# SCH_Instrumenta_o-Eletronica.net
KiCad netlist of a schematic drawn in EasyEDA
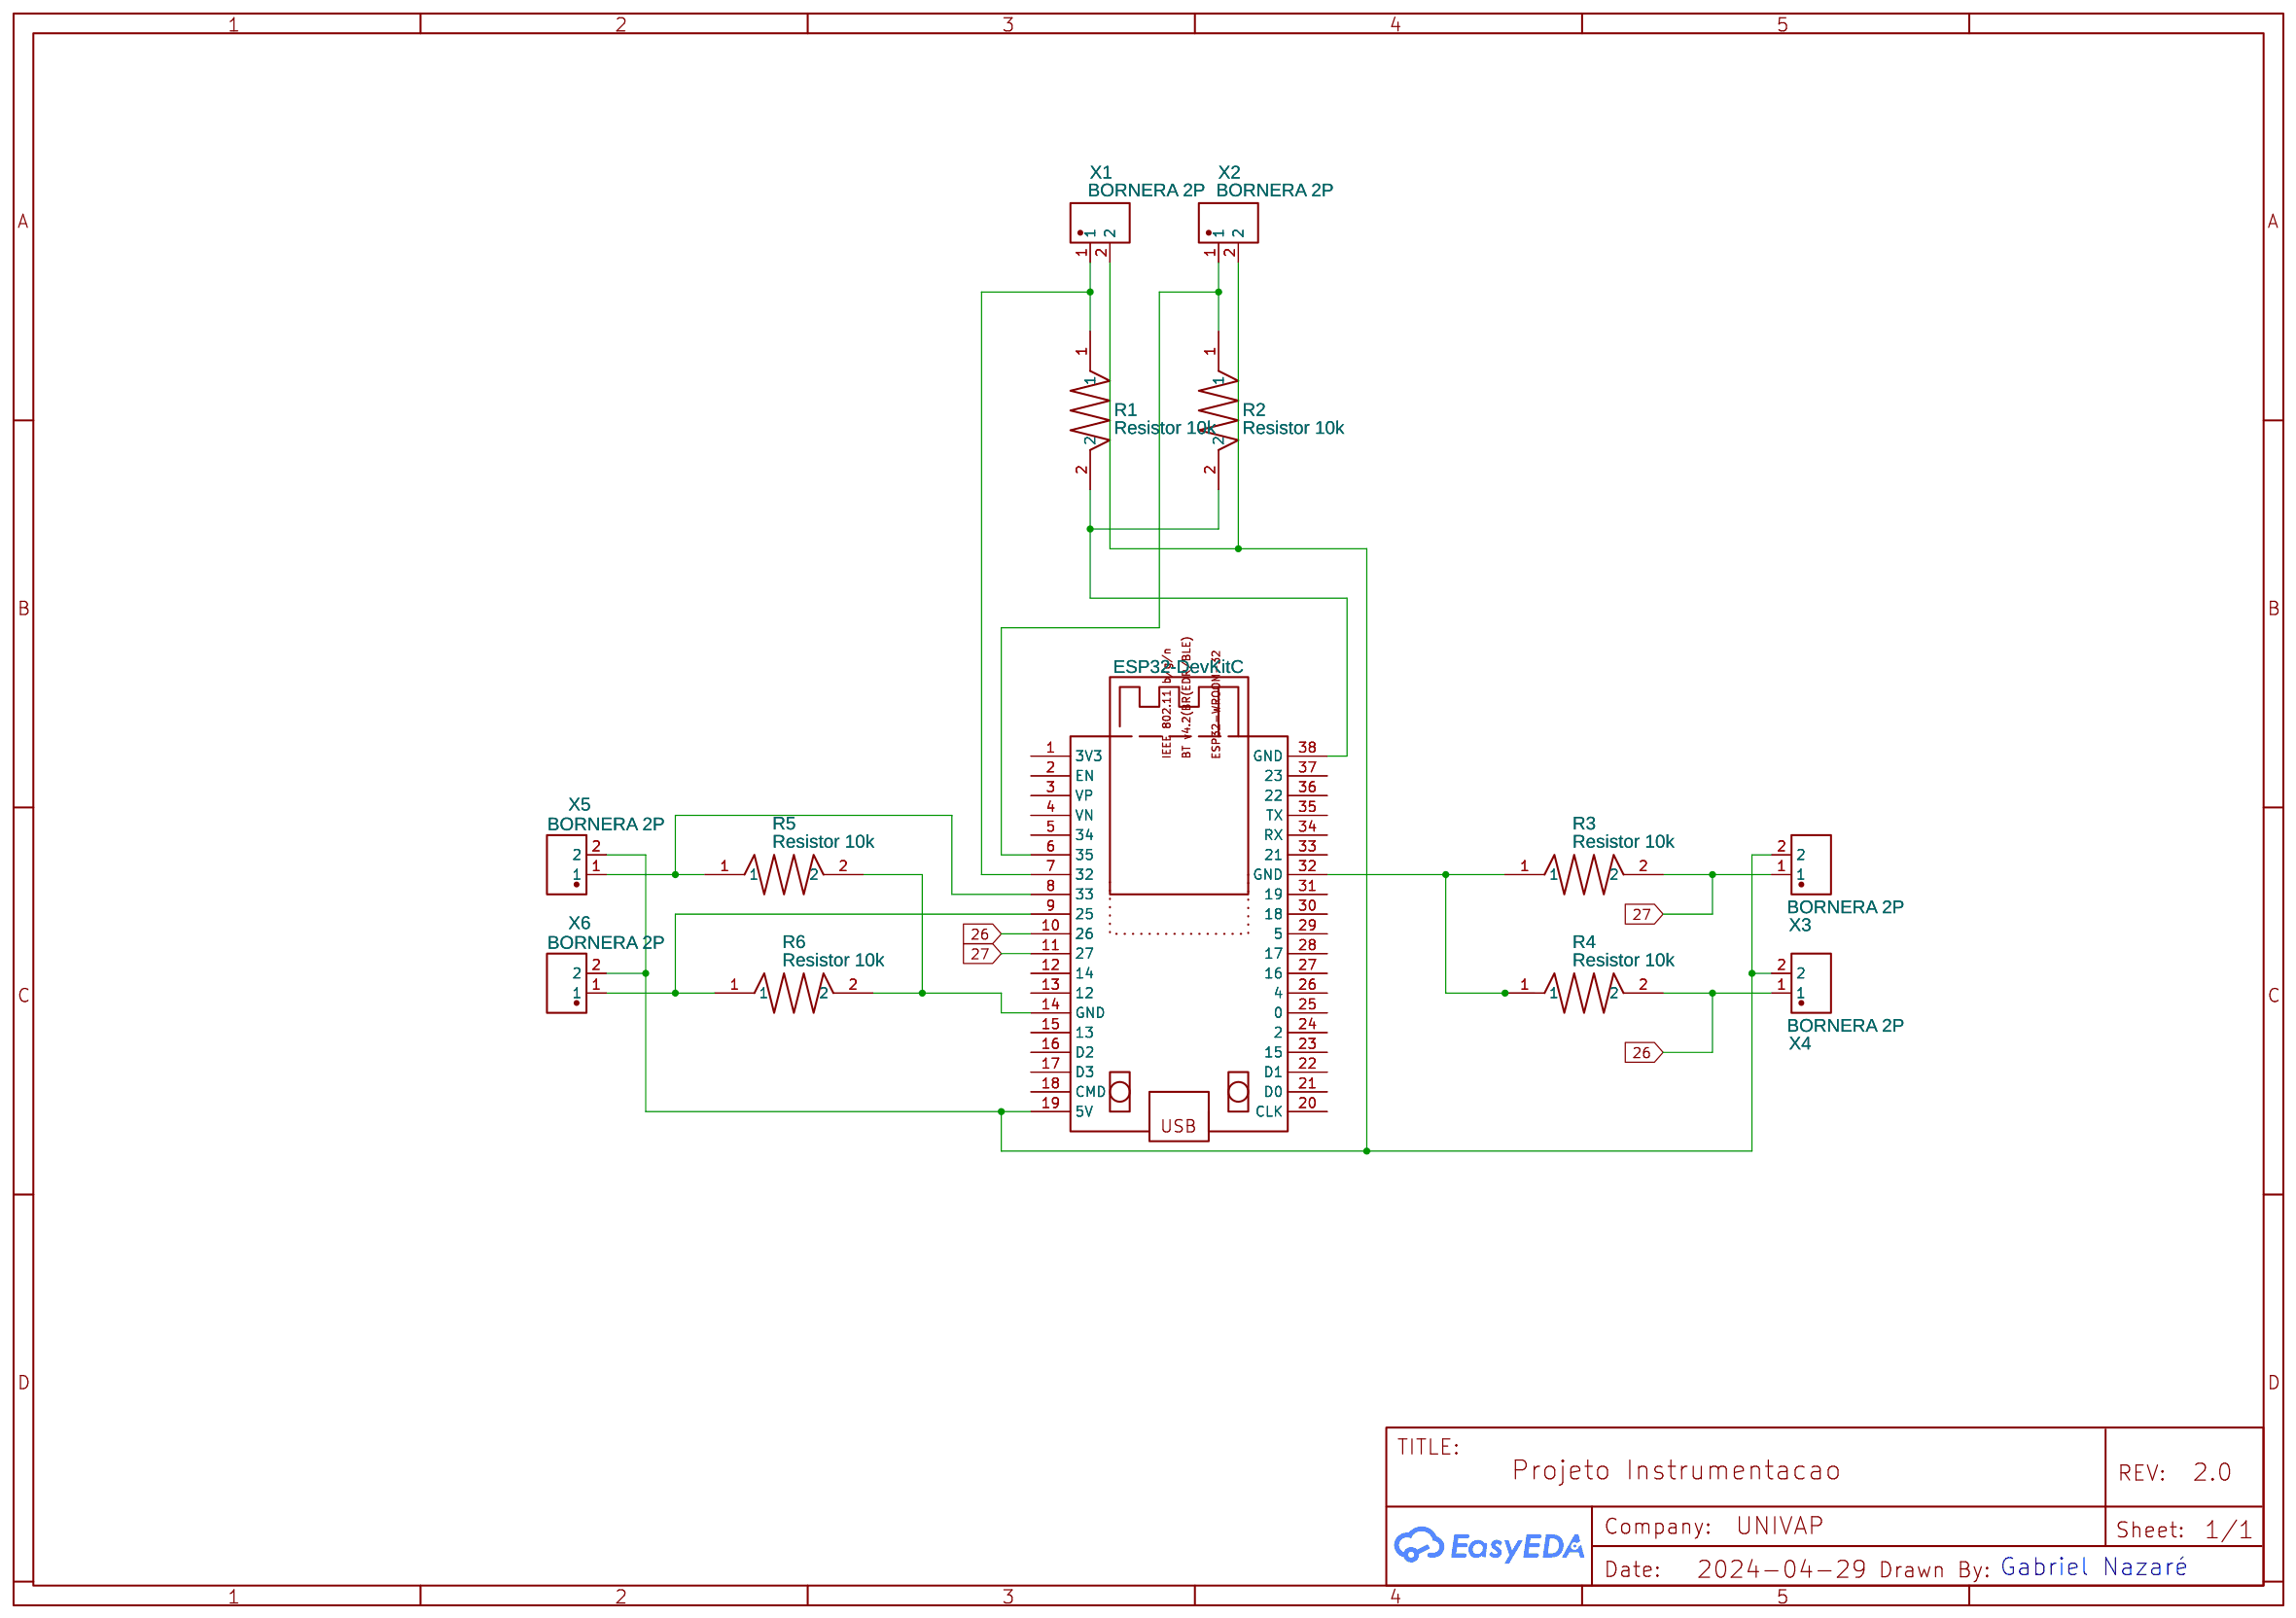
[diagram p0: schematic sheet]

(export (version "E")
  (design (tool "Eeschema 10.0.6"))
  (components
    (comp (ref "R1") (value "Resistor 10k") (libsource (lib "") (part "Resistor 10k_1")))
    (comp (ref "R2") (value "Resistor 10k") (libsource (lib "") (part "Resistor 10k_1")))
    (comp (ref "R3") (value "Resistor 10k") (libsource (lib "") (part "Resistor 10k")))
    (comp (ref "R4") (value "Resistor 10k") (libsource (lib "") (part "Resistor 10k")))
    (comp (ref "R5") (value "Resistor 10k") (libsource (lib "") (part "Resistor 10k")))
    (comp (ref "R6") (value "Resistor 10k") (libsource (lib "") (part "Resistor 10k")))
    (comp (ref "U1")
      (value "ESP32-DevKitC")
      (fields (field (name "Manufacturer") "Espressif Systems"))
      (libsource (lib "") (part "ESP32-DevKitC"))
    )
    (comp (ref "X1") (value "BORNERA 2P") (libsource (lib "") (part "BORNERA 2P_2")))
    (comp (ref "X2") (value "BORNERA 2P") (libsource (lib "") (part "BORNERA 2P_2")))
    (comp (ref "X3") (value "BORNERA 2P") (libsource (lib "") (part "BORNERA 2P")))
    (comp (ref "X4") (value "BORNERA 2P") (libsource (lib "") (part "BORNERA 2P")))
    (comp (ref "X5") (value "BORNERA 2P") (libsource (lib "") (part "BORNERA 2P_1")))
    (comp (ref "X6") (value "BORNERA 2P") (libsource (lib "") (part "BORNERA 2P_1")))
  )
  (nets
    (net (code "1") (name "26") (class "Default")
      (node (ref "R4") (pin "2") (pinfunction "2_2") (pintype "unspecified"))
      (node (ref "U1") (pin "10") (pinfunction "26_10") (pintype "unspecified"))
      (node (ref "X4") (pin "1") (pinfunction "1_1") (pintype "unspecified"))
    )
    (net (code "2") (name "27") (class "Default")
      (node (ref "R3") (pin "2") (pinfunction "2_2") (pintype "unspecified"))
      (node (ref "U1") (pin "11") (pinfunction "27_11") (pintype "unspecified"))
      (node (ref "X3") (pin "1") (pinfunction "1_1") (pintype "unspecified"))
    )
    (net (code "3") (name "Net-(R1-Pad2)") (class "Default")
      (node (ref "R1") (pin "2") (pinfunction "2_2") (pintype "unspecified"))
      (node (ref "R2") (pin "2") (pinfunction "2_2") (pintype "unspecified"))
      (node (ref "U1") (pin "38") (pinfunction "GND_38") (pintype "unspecified"))
    )
    (net (code "4") (name "Net-(R3-Pad1)") (class "Default")
      (node (ref "R3") (pin "1") (pinfunction "1_1") (pintype "unspecified"))
      (node (ref "R4") (pin "1") (pinfunction "1_1") (pintype "unspecified"))
      (node (ref "U1") (pin "32") (pinfunction "GND_32") (pintype "unspecified"))
    )
    (net (code "5") (name "Net-(R5-Pad2)") (class "Default")
      (node (ref "R5") (pin "2") (pinfunction "2_2") (pintype "unspecified"))
      (node (ref "R6") (pin "2") (pinfunction "2_2") (pintype "unspecified"))
      (node (ref "U1") (pin "14") (pinfunction "GND_14") (pintype "unspecified"))
    )
    (net (code "6") (name "Net-(U1-5V)") (class "Default")
      (node (ref "U1") (pin "19") (pinfunction "5V_19") (pintype "unspecified"))
      (node (ref "X1") (pin "2") (pinfunction "2_2") (pintype "unspecified"))
      (node (ref "X2") (pin "2") (pinfunction "2_2") (pintype "unspecified"))
      (node (ref "X3") (pin "2") (pinfunction "2_2") (pintype "unspecified"))
      (node (ref "X4") (pin "2") (pinfunction "2_2") (pintype "unspecified"))
      (node (ref "X5") (pin "2") (pinfunction "2_2") (pintype "unspecified"))
      (node (ref "X6") (pin "2") (pinfunction "2_2") (pintype "unspecified"))
    )
    (net (code "7") (name "Net-(U1-25)") (class "Default")
      (node (ref "R6") (pin "1") (pinfunction "1_1") (pintype "unspecified"))
      (node (ref "U1") (pin "9") (pinfunction "25_9") (pintype "unspecified"))
      (node (ref "X6") (pin "1") (pinfunction "1_1") (pintype "unspecified"))
    )
    (net (code "8") (name "Net-(U1-32)") (class "Default")
      (node (ref "R1") (pin "1") (pinfunction "1_1") (pintype "unspecified"))
      (node (ref "U1") (pin "7") (pinfunction "32_7") (pintype "unspecified"))
      (node (ref "X1") (pin "1") (pinfunction "1_1") (pintype "unspecified"))
    )
    (net (code "9") (name "Net-(U1-33)") (class "Default")
      (node (ref "R5") (pin "1") (pinfunction "1_1") (pintype "unspecified"))
      (node (ref "U1") (pin "8") (pinfunction "33_8") (pintype "unspecified"))
      (node (ref "X5") (pin "1") (pinfunction "1_1") (pintype "unspecified"))
    )
    (net (code "10") (name "Net-(U1-35)") (class "Default")
      (node (ref "R2") (pin "1") (pinfunction "1_1") (pintype "unspecified"))
      (node (ref "U1") (pin "6") (pinfunction "35_6") (pintype "unspecified"))
      (node (ref "X2") (pin "1") (pinfunction "1_1") (pintype "unspecified"))
    )
    (net (code "11") (name "unconnected-(U1-0-Pad25)") (class "Default")
      (node (ref "U1") (pin "25") (pinfunction "0_25") (pintype "unspecified"))
    )
    (net (code "12") (name "unconnected-(U1-2-Pad24)") (class "Default")
      (node (ref "U1") (pin "24") (pinfunction "2_24") (pintype "unspecified"))
    )
    (net (code "13") (name "unconnected-(U1-3V3-Pad1)") (class "Default")
      (node (ref "U1") (pin "1") (pinfunction "3V3_1") (pintype "unspecified"))
    )
    (net (code "14") (name "unconnected-(U1-4-Pad26)") (class "Default")
      (node (ref "U1") (pin "26") (pinfunction "4_26") (pintype "unspecified"))
    )
    (net (code "15") (name "unconnected-(U1-5-Pad29)") (class "Default")
      (node (ref "U1") (pin "29") (pinfunction "5_29") (pintype "unspecified"))
    )
    (net (code "16") (name "unconnected-(U1-12-Pad13)") (class "Default")
      (node (ref "U1") (pin "13") (pinfunction "12_13") (pintype "unspecified"))
    )
    (net (code "17") (name "unconnected-(U1-13-Pad15)") (class "Default")
      (node (ref "U1") (pin "15") (pinfunction "13_15") (pintype "unspecified"))
    )
    (net (code "18") (name "unconnected-(U1-14-Pad12)") (class "Default")
      (node (ref "U1") (pin "12") (pinfunction "14_12") (pintype "unspecified"))
    )
    (net (code "19") (name "unconnected-(U1-15-Pad23)") (class "Default")
      (node (ref "U1") (pin "23") (pinfunction "15_23") (pintype "unspecified"))
    )
    (net (code "20") (name "unconnected-(U1-16-Pad27)") (class "Default")
      (node (ref "U1") (pin "27") (pinfunction "16_27") (pintype "unspecified"))
    )
    (net (code "21") (name "unconnected-(U1-17-Pad28)") (class "Default")
      (node (ref "U1") (pin "28") (pinfunction "17_28") (pintype "unspecified"))
    )
    (net (code "22") (name "unconnected-(U1-18-Pad30)") (class "Default")
      (node (ref "U1") (pin "30") (pinfunction "18_30") (pintype "unspecified"))
    )
    (net (code "23") (name "unconnected-(U1-19-Pad31)") (class "Default")
      (node (ref "U1") (pin "31") (pinfunction "19_31") (pintype "unspecified"))
    )
    (net (code "24") (name "unconnected-(U1-21-Pad33)") (class "Default")
      (node (ref "U1") (pin "33") (pinfunction "21_33") (pintype "unspecified"))
    )
    (net (code "25") (name "unconnected-(U1-22-Pad36)") (class "Default")
      (node (ref "U1") (pin "36") (pinfunction "22_36") (pintype "unspecified"))
    )
    (net (code "26") (name "unconnected-(U1-23-Pad37)") (class "Default")
      (node (ref "U1") (pin "37") (pinfunction "23_37") (pintype "unspecified"))
    )
    (net (code "27") (name "unconnected-(U1-34-Pad5)") (class "Default")
      (node (ref "U1") (pin "5") (pinfunction "34_5") (pintype "unspecified"))
    )
    (net (code "28") (name "unconnected-(U1-CLK-Pad20)") (class "Default")
      (node (ref "U1") (pin "20") (pinfunction "CLK_20") (pintype "unspecified"))
    )
    (net (code "29") (name "unconnected-(U1-CMD-Pad18)") (class "Default")
      (node (ref "U1") (pin "18") (pinfunction "CMD_18") (pintype "unspecified"))
    )
    (net (code "30") (name "unconnected-(U1-D0-Pad21)") (class "Default")
      (node (ref "U1") (pin "21") (pinfunction "D0_21") (pintype "unspecified"))
    )
    (net (code "31") (name "unconnected-(U1-D1-Pad22)") (class "Default")
      (node (ref "U1") (pin "22") (pinfunction "D1_22") (pintype "unspecified"))
    )
    (net (code "32") (name "unconnected-(U1-D2-Pad16)") (class "Default")
      (node (ref "U1") (pin "16") (pinfunction "D2_16") (pintype "unspecified"))
    )
    (net (code "33") (name "unconnected-(U1-D3-Pad17)") (class "Default")
      (node (ref "U1") (pin "17") (pinfunction "D3_17") (pintype "unspecified"))
    )
    (net (code "34") (name "unconnected-(U1-EN-Pad2)") (class "Default")
      (node (ref "U1") (pin "2") (pinfunction "EN_2") (pintype "unspecified"))
    )
    (net (code "35") (name "unconnected-(U1-RX-Pad34)") (class "Default")
      (node (ref "U1") (pin "34") (pinfunction "RX_34") (pintype "unspecified"))
    )
    (net (code "36") (name "unconnected-(U1-TX-Pad35)") (class "Default")
      (node (ref "U1") (pin "35") (pinfunction "TX_35") (pintype "unspecified"))
    )
    (net (code "37") (name "unconnected-(U1-VN-Pad4)") (class "Default")
      (node (ref "U1") (pin "4") (pinfunction "VN_4") (pintype "unspecified"))
    )
    (net (code "38") (name "unconnected-(U1-VP-Pad3)") (class "Default")
      (node (ref "U1") (pin "3") (pinfunction "VP_3") (pintype "unspecified"))
    )
  )
)
